# 03_SAM2195.net
KiCad netlist of a schematic drawn in Altium Designer
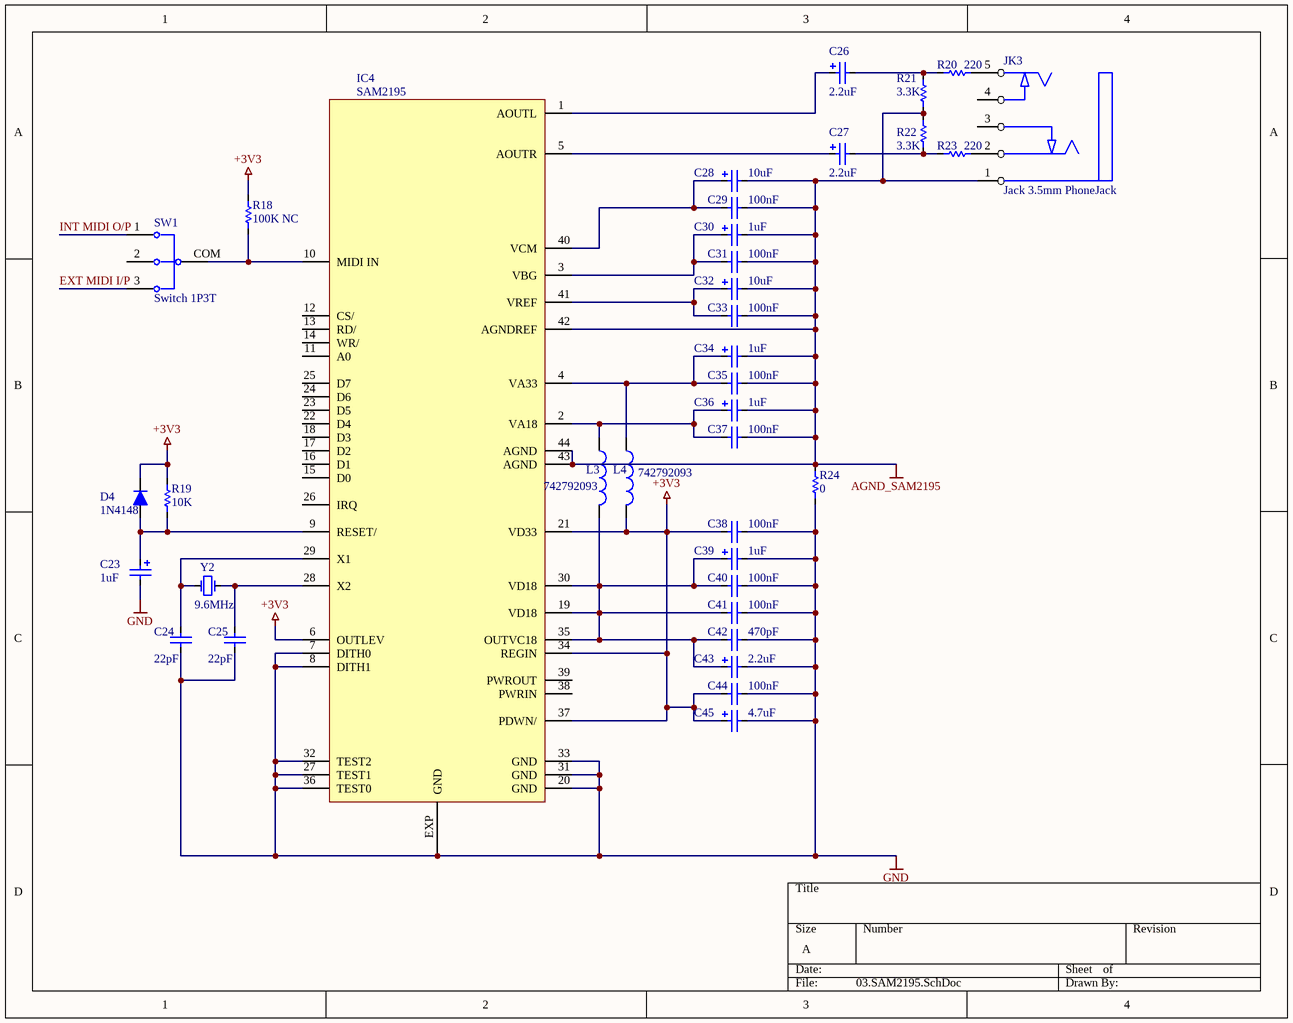
[diagram p0: 03.SAM2195.SchDoc]

(export (version "E")
  (design (tool "Eeschema 10.0.6"))
  (components
    (comp (ref "C23")
      (value "1uF")
      (footprint "Cap SMD 4x5.3")
      (libsource (lib "MainnoLab library") (part "Capacitor Polar"))
    )
    (comp (ref "C24")
      (value "22pF")
      (footprint "C0603-ROUND")
      (libsource (lib "MainnoLab library") (part "Capacitor Non-Polar"))
    )
    (comp (ref "C25")
      (value "22pF")
      (footprint "C0603-ROUND")
      (libsource (lib "MainnoLab library") (part "Capacitor Non-Polar"))
    )
    (comp (ref "C26")
      (value "2.2uF")
      (footprint "Cap SMD 4x5.3")
      (libsource (lib "MainnoLab library") (part "Capacitor Polar"))
    )
    (comp (ref "C27")
      (value "2.2uF")
      (footprint "Cap SMD 4x5.3")
      (libsource (lib "MainnoLab library") (part "Capacitor Polar"))
    )
    (comp (ref "C28")
      (value "10uF")
      (footprint "Cap SMD 4x5.3")
      (libsource (lib "MainnoLab library") (part "Capacitor Polar"))
    )
    (comp (ref "C29")
      (value "100nF")
      (footprint "C0603-ROUND")
      (libsource (lib "MainnoLab library") (part "Capacitor Non-Polar"))
    )
    (comp (ref "C30")
      (value "1uF")
      (footprint "Cap SMD 4x5.3")
      (libsource (lib "MainnoLab library") (part "Capacitor Polar"))
    )
    (comp (ref "C31")
      (value "100nF")
      (footprint "C0603-ROUND")
      (libsource (lib "MainnoLab library") (part "Capacitor Non-Polar"))
    )
    (comp (ref "C32")
      (value "10uF")
      (footprint "Cap SMD 4x5.3")
      (libsource (lib "MainnoLab library") (part "Capacitor Polar"))
    )
    (comp (ref "C33")
      (value "100nF")
      (footprint "C0603-ROUND")
      (libsource (lib "MainnoLab library") (part "Capacitor Non-Polar"))
    )
    (comp (ref "C34")
      (value "1uF")
      (footprint "Cap SMD 4x5.3")
      (libsource (lib "MainnoLab library") (part "Capacitor Polar"))
    )
    (comp (ref "C35")
      (value "100nF")
      (footprint "C0603-ROUND")
      (libsource (lib "MainnoLab library") (part "Capacitor Non-Polar"))
    )
    (comp (ref "C36")
      (value "1uF")
      (footprint "Cap SMD 4x5.3")
      (libsource (lib "MainnoLab library") (part "Capacitor Polar"))
    )
    (comp (ref "C37")
      (value "100nF")
      (footprint "C0603-ROUND")
      (libsource (lib "MainnoLab library") (part "Capacitor Non-Polar"))
    )
    (comp (ref "C38")
      (value "100nF")
      (footprint "C0603-ROUND")
      (libsource (lib "MainnoLab library") (part "Capacitor Non-Polar"))
    )
    (comp (ref "C39")
      (value "1uF")
      (footprint "Cap SMD 4x5.3")
      (libsource (lib "MainnoLab library") (part "Capacitor Polar"))
    )
    (comp (ref "C40")
      (value "100nF")
      (footprint "C0603-ROUND")
      (libsource (lib "MainnoLab library") (part "Capacitor Non-Polar"))
    )
    (comp (ref "C41")
      (value "100nF")
      (footprint "C0603-ROUND")
      (libsource (lib "MainnoLab library") (part "Capacitor Non-Polar"))
    )
    (comp (ref "C42")
      (value "470pF")
      (footprint "C0603-ROUND")
      (libsource (lib "MainnoLab library") (part "Capacitor Non-Polar"))
    )
    (comp (ref "C43")
      (value "2.2uF")
      (footprint "Cap SMD 4x5.3")
      (libsource (lib "MainnoLab library") (part "Capacitor Polar"))
    )
    (comp (ref "C44")
      (value "100nF")
      (footprint "C0603-ROUND")
      (libsource (lib "MainnoLab library") (part "Capacitor Non-Polar"))
    )
    (comp (ref "C45")
      (value "4.7uF")
      (footprint "Cap SMD 4x5.3")
      (libsource (lib "MainnoLab library") (part "Capacitor Polar"))
    )
    (comp (ref "D4")
      (value "1N4148")
      (footprint "SOD-323")
      (libsource (lib "MainnoLab library") (part "Diode 1N4148"))
    )
    (comp (ref "IC4") (value "SAM2195") (libsource (lib "MainnoLab library") (part "IC SAM2195")))
    (comp (ref "JK3")
      (value "Jack 3.5mm PhoneJack")
      (footprint "PhoneJack EJ05-06-PF")
      (libsource (lib "MainnoLab library") (part "Jack 3.5mm PhoneJack"))
    )
    (comp (ref "L3")
      (value "742792093")
      (footprint "0805")
      (description "Inductor")
      (fields (field (name "PUBLISHER") "Altium Limited"))
      (libsource (lib "Miscellaneous Devices") (part "Inductor"))
    )
    (comp (ref "L4")
      (value "742792093")
      (footprint "0805")
      (description "Inductor")
      (fields (field (name "PUBLISHER") "Altium Limited"))
      (libsource (lib "Miscellaneous Devices") (part "Inductor"))
    )
    (comp (ref "R18")
      (value "100K NC")
      (footprint "R0603-ROUND")
      (libsource (lib "MainnoLab library") (part "Resistor"))
    )
    (comp (ref "R19")
      (value "10K")
      (footprint "R0603-ROUND")
      (libsource (lib "MainnoLab library") (part "Resistor"))
    )
    (comp (ref "R20")
      (value "220")
      (footprint "R0603-ROUND")
      (libsource (lib "MainnoLab library") (part "Resistor"))
    )
    (comp (ref "R21")
      (value "3.3K")
      (footprint "R0603-ROUND")
      (libsource (lib "MainnoLab library") (part "Resistor"))
    )
    (comp (ref "R22")
      (value "3.3K")
      (footprint "R0603-ROUND")
      (libsource (lib "MainnoLab library") (part "Resistor"))
    )
    (comp (ref "R23")
      (value "220")
      (footprint "R0603-ROUND")
      (libsource (lib "MainnoLab library") (part "Resistor"))
    )
    (comp (ref "R24")
      (value "0")
      (footprint "R0603-ROUND")
      (libsource (lib "MainnoLab library") (part "Resistor"))
    )
    (comp (ref "SW1")
      (value "Switch 1P3T")
      (footprint "SW 1P3T - SS13D01")
      (libsource (lib "MainnoLab library") (part "Switch 1P3T"))
    )
    (comp (ref "Y2")
      (value "9.6MHz")
      (footprint "HC-49S DIP")
      (libsource (lib "MainnoLab library") (part "Crystal"))
    )
  )
  (nets
    (net (code "1") (name "+3V3") (class "Default")
      (node (ref "C38") (pin "1") (pinfunction "1_1") (pintype "passive"))
      (node (ref "C44") (pin "1") (pinfunction "1_1") (pintype "passive"))
      (node (ref "C45") (pin "1") (pinfunction "1_1") (pintype "passive"))
      (node (ref "D4") (pin "2") (pinfunction "2_2") (pintype "passive"))
      (node (ref "IC4") (pin "21") (pinfunction "VD33_21") (pintype "passive"))
      (node (ref "IC4") (pin "34") (pinfunction "REGIN_34") (pintype "passive"))
      (node (ref "IC4") (pin "37") (pinfunction "PDWN/_37") (pintype "passive"))
      (node (ref "IC4") (pin "6") (pinfunction "OUTLEV_6") (pintype "passive"))
      (node (ref "L4") (pin "1") (pinfunction "1_1") (pintype "passive"))
      (node (ref "R18") (pin "1") (pinfunction "1_1") (pintype "passive"))
      (node (ref "R19") (pin "2") (pinfunction "2_2") (pintype "passive"))
    )
    (net (code "2") (name "/EXT MIDI I{slash}P") (class "Default")
      (node (ref "SW1") (pin "3") (pinfunction "3_3") (pintype "passive"))
    )
    (net (code "3") (name "/INT MIDI O{slash}P") (class "Default")
      (node (ref "SW1") (pin "1") (pinfunction "1_1") (pintype "passive"))
    )
    (net (code "4") (name "AGND_SAM2195") (class "Default")
      (node (ref "C28") (pin "2") (pinfunction "2_2") (pintype "passive"))
      (node (ref "C29") (pin "2") (pinfunction "2_2") (pintype "passive"))
      (node (ref "C30") (pin "2") (pinfunction "2_2") (pintype "passive"))
      (node (ref "C31") (pin "2") (pinfunction "2_2") (pintype "passive"))
      (node (ref "C32") (pin "2") (pinfunction "2_2") (pintype "passive"))
      (node (ref "C33") (pin "2") (pinfunction "2_2") (pintype "passive"))
      (node (ref "C34") (pin "2") (pinfunction "2_2") (pintype "passive"))
      (node (ref "C35") (pin "2") (pinfunction "2_2") (pintype "passive"))
      (node (ref "C36") (pin "2") (pinfunction "2_2") (pintype "passive"))
      (node (ref "C37") (pin "2") (pinfunction "2_2") (pintype "passive"))
      (node (ref "IC4") (pin "42") (pinfunction "AGNDREF_42") (pintype "passive"))
      (node (ref "IC4") (pin "43") (pinfunction "AGND_43") (pintype "passive"))
      (node (ref "IC4") (pin "44") (pinfunction "AGND_44") (pintype "passive"))
      (node (ref "JK3") (pin "1") (pinfunction "1_1") (pintype "passive"))
      (node (ref "R21") (pin "2") (pinfunction "2_2") (pintype "passive"))
      (node (ref "R22") (pin "1") (pinfunction "1_1") (pintype "passive"))
      (node (ref "R24") (pin "2") (pinfunction "2_2") (pintype "passive"))
    )
    (net (code "5") (name "GND") (class "Default")
      (node (ref "C23") (pin "2") (pinfunction "2_2") (pintype "passive"))
      (node (ref "C24") (pin "1") (pinfunction "1_1") (pintype "passive"))
      (node (ref "C25") (pin "1") (pinfunction "1_1") (pintype "passive"))
      (node (ref "C38") (pin "2") (pinfunction "2_2") (pintype "passive"))
      (node (ref "C39") (pin "2") (pinfunction "2_2") (pintype "passive"))
      (node (ref "C40") (pin "2") (pinfunction "2_2") (pintype "passive"))
      (node (ref "C41") (pin "2") (pinfunction "2_2") (pintype "passive"))
      (node (ref "C42") (pin "2") (pinfunction "2_2") (pintype "passive"))
      (node (ref "C43") (pin "2") (pinfunction "2_2") (pintype "passive"))
      (node (ref "C44") (pin "2") (pinfunction "2_2") (pintype "passive"))
      (node (ref "C45") (pin "2") (pinfunction "2_2") (pintype "passive"))
      (node (ref "IC4") (pin "20") (pinfunction "GND_20") (pintype "passive"))
      (node (ref "IC4") (pin "27") (pinfunction "TEST1_27") (pintype "passive"))
      (node (ref "IC4") (pin "31") (pinfunction "GND_31") (pintype "passive"))
      (node (ref "IC4") (pin "32") (pinfunction "TEST2_32") (pintype "passive"))
      (node (ref "IC4") (pin "33") (pinfunction "GND_33") (pintype "passive"))
      (node (ref "IC4") (pin "36") (pinfunction "TEST0_36") (pintype "passive"))
      (node (ref "IC4") (pin "7") (pinfunction "DITH0_7") (pintype "passive"))
      (node (ref "IC4") (pin "8") (pinfunction "DITH1_8") (pintype "passive"))
      (node (ref "IC4") (pin "EXP") (pinfunction "GND_EXP") (pintype "passive"))
      (node (ref "R24") (pin "1") (pinfunction "1_1") (pintype "passive"))
    )
    (net (code "6") (name "Net-(C26-Pad2)") (class "Default")
      (node (ref "C26") (pin "2") (pinfunction "2_2") (pintype "passive"))
      (node (ref "R20") (pin "2") (pinfunction "2_2") (pintype "passive"))
      (node (ref "R21") (pin "1") (pinfunction "1_1") (pintype "passive"))
    )
    (net (code "7") (name "Net-(C27-Pad2)") (class "Default")
      (node (ref "C27") (pin "2") (pinfunction "2_2") (pintype "passive"))
      (node (ref "R22") (pin "2") (pinfunction "2_2") (pintype "passive"))
      (node (ref "R23") (pin "2") (pinfunction "2_2") (pintype "passive"))
    )
    (net (code "8") (name "Net-(IC4-AOUTL)") (class "Default")
      (node (ref "C26") (pin "1") (pinfunction "1_1") (pintype "passive"))
      (node (ref "IC4") (pin "1") (pinfunction "AOUTL_1") (pintype "passive"))
    )
    (net (code "9") (name "Net-(IC4-AOUTR)") (class "Default")
      (node (ref "C27") (pin "1") (pinfunction "1_1") (pintype "passive"))
      (node (ref "IC4") (pin "5") (pinfunction "AOUTR_5") (pintype "passive"))
    )
    (net (code "10") (name "Net-(IC4-MIDI_IN)") (class "Default")
      (node (ref "IC4") (pin "10") (pinfunction "MIDI_IN_10") (pintype "passive"))
      (node (ref "R18") (pin "2") (pinfunction "2_2") (pintype "passive"))
      (node (ref "SW1") (pin "COM") (pinfunction "COMMON1_COM") (pintype "passive"))
    )
    (net (code "11") (name "Net-(IC4-OUTVC18)") (class "Default")
      (node (ref "C39") (pin "1") (pinfunction "1_1") (pintype "passive"))
      (node (ref "C40") (pin "1") (pinfunction "1_1") (pintype "passive"))
      (node (ref "C41") (pin "1") (pinfunction "1_1") (pintype "passive"))
      (node (ref "C42") (pin "1") (pinfunction "1_1") (pintype "passive"))
      (node (ref "C43") (pin "1") (pinfunction "1_1") (pintype "passive"))
      (node (ref "IC4") (pin "19") (pinfunction "VD18_19") (pintype "passive"))
      (node (ref "IC4") (pin "30") (pinfunction "VD18_30") (pintype "passive"))
      (node (ref "IC4") (pin "35") (pinfunction "OUTVC18_35") (pintype "passive"))
      (node (ref "L3") (pin "1") (pinfunction "1_1") (pintype "passive"))
    )
    (net (code "12") (name "Net-(IC4-RESET{slash})") (class "Default")
      (node (ref "C23") (pin "1") (pinfunction "1_1") (pintype "passive"))
      (node (ref "D4") (pin "1") (pinfunction "1_1") (pintype "passive"))
      (node (ref "IC4") (pin "9") (pinfunction "RESET/_9") (pintype "passive"))
      (node (ref "R19") (pin "1") (pinfunction "1_1") (pintype "passive"))
    )
    (net (code "13") (name "Net-(IC4-VA18)") (class "Default")
      (node (ref "C36") (pin "1") (pinfunction "1_1") (pintype "passive"))
      (node (ref "C37") (pin "1") (pinfunction "1_1") (pintype "passive"))
      (node (ref "IC4") (pin "2") (pinfunction "VA18_2") (pintype "passive"))
      (node (ref "L3") (pin "2") (pinfunction "2_2") (pintype "passive"))
    )
    (net (code "14") (name "Net-(IC4-VA33)") (class "Default")
      (node (ref "C34") (pin "1") (pinfunction "1_1") (pintype "passive"))
      (node (ref "C35") (pin "1") (pinfunction "1_1") (pintype "passive"))
      (node (ref "IC4") (pin "4") (pinfunction "VA33_4") (pintype "passive"))
      (node (ref "L4") (pin "2") (pinfunction "2_2") (pintype "passive"))
    )
    (net (code "15") (name "Net-(IC4-VBG)") (class "Default")
      (node (ref "C30") (pin "1") (pinfunction "1_1") (pintype "passive"))
      (node (ref "C31") (pin "1") (pinfunction "1_1") (pintype "passive"))
      (node (ref "IC4") (pin "3") (pinfunction "VBG_3") (pintype "passive"))
    )
    (net (code "16") (name "Net-(IC4-VCM)") (class "Default")
      (node (ref "C28") (pin "1") (pinfunction "1_1") (pintype "passive"))
      (node (ref "C29") (pin "1") (pinfunction "1_1") (pintype "passive"))
      (node (ref "IC4") (pin "40") (pinfunction "VCM_40") (pintype "passive"))
    )
    (net (code "17") (name "Net-(IC4-VREF)") (class "Default")
      (node (ref "C32") (pin "1") (pinfunction "1_1") (pintype "passive"))
      (node (ref "C33") (pin "1") (pinfunction "1_1") (pintype "passive"))
      (node (ref "IC4") (pin "41") (pinfunction "VREF_41") (pintype "passive"))
    )
    (net (code "18") (name "Net-(IC4-X1)") (class "Default")
      (node (ref "C24") (pin "2") (pinfunction "2_2") (pintype "passive"))
      (node (ref "IC4") (pin "29") (pinfunction "X1_29") (pintype "passive"))
      (node (ref "Y2") (pin "2") (pinfunction "2_2") (pintype "passive"))
    )
    (net (code "19") (name "Net-(IC4-X2)") (class "Default")
      (node (ref "C25") (pin "2") (pinfunction "2_2") (pintype "passive"))
      (node (ref "IC4") (pin "28") (pinfunction "X2_28") (pintype "passive"))
      (node (ref "Y2") (pin "1") (pinfunction "1_1") (pintype "passive"))
    )
    (net (code "20") (name "Net-(JK3-Pad2)") (class "Default")
      (node (ref "JK3") (pin "2") (pinfunction "2_2") (pintype "passive"))
      (node (ref "R23") (pin "1") (pinfunction "1_1") (pintype "passive"))
    )
    (net (code "21") (name "Net-(JK3-Pad5)") (class "Default")
      (node (ref "JK3") (pin "5") (pinfunction "5_5") (pintype "passive"))
      (node (ref "R20") (pin "1") (pinfunction "1_1") (pintype "passive"))
    )
    (net (code "22") (name "unconnected-(IC4-A0-Pad11)") (class "Default")
      (node (ref "IC4") (pin "11") (pinfunction "A0_11") (pintype "passive"))
    )
    (net (code "23") (name "unconnected-(IC4-CS{slash}-Pad12)") (class "Default")
      (node (ref "IC4") (pin "12") (pinfunction "CS/_12") (pintype "passive"))
    )
    (net (code "24") (name "unconnected-(IC4-D0-Pad15)") (class "Default")
      (node (ref "IC4") (pin "15") (pinfunction "D0_15") (pintype "passive"))
    )
    (net (code "25") (name "unconnected-(IC4-D1-Pad16)") (class "Default")
      (node (ref "IC4") (pin "16") (pinfunction "D1_16") (pintype "passive"))
    )
    (net (code "26") (name "unconnected-(IC4-D2-Pad17)") (class "Default")
      (node (ref "IC4") (pin "17") (pinfunction "D2_17") (pintype "passive"))
    )
    (net (code "27") (name "unconnected-(IC4-D3-Pad18)") (class "Default")
      (node (ref "IC4") (pin "18") (pinfunction "D3_18") (pintype "passive"))
    )
    (net (code "28") (name "unconnected-(IC4-D4-Pad22)") (class "Default")
      (node (ref "IC4") (pin "22") (pinfunction "D4_22") (pintype "passive"))
    )
    (net (code "29") (name "unconnected-(IC4-D5-Pad23)") (class "Default")
      (node (ref "IC4") (pin "23") (pinfunction "D5_23") (pintype "passive"))
    )
    (net (code "30") (name "unconnected-(IC4-D6-Pad24)") (class "Default")
      (node (ref "IC4") (pin "24") (pinfunction "D6_24") (pintype "passive"))
    )
    (net (code "31") (name "unconnected-(IC4-D7-Pad25)") (class "Default")
      (node (ref "IC4") (pin "25") (pinfunction "D7_25") (pintype "passive"))
    )
    (net (code "32") (name "unconnected-(IC4-IRQ-Pad26)") (class "Default")
      (node (ref "IC4") (pin "26") (pinfunction "IRQ_26") (pintype "passive"))
    )
    (net (code "33") (name "unconnected-(IC4-PWRIN-Pad38)") (class "Default")
      (node (ref "IC4") (pin "38") (pinfunction "PWRIN_38") (pintype "passive"))
    )
    (net (code "34") (name "unconnected-(IC4-PWROUT-Pad39)") (class "Default")
      (node (ref "IC4") (pin "39") (pinfunction "PWROUT_39") (pintype "passive"))
    )
    (net (code "35") (name "unconnected-(IC4-RD{slash}-Pad13)") (class "Default")
      (node (ref "IC4") (pin "13") (pinfunction "RD/_13") (pintype "passive"))
    )
    (net (code "36") (name "unconnected-(IC4-WR{slash}-Pad14)") (class "Default")
      (node (ref "IC4") (pin "14") (pinfunction "WR/_14") (pintype "passive"))
    )
    (net (code "37") (name "unconnected-(JK3-Pad3)") (class "Default")
      (node (ref "JK3") (pin "3") (pinfunction "3_3") (pintype "passive"))
    )
    (net (code "38") (name "unconnected-(JK3-Pad4)") (class "Default")
      (node (ref "JK3") (pin "4") (pinfunction "4_4") (pintype "passive"))
    )
    (net (code "39") (name "unconnected-(SW1-Pad2)") (class "Default")
      (node (ref "SW1") (pin "2") (pinfunction "2_2") (pintype "passive"))
    )
  )
)
